# remote_control.net
KiCad netlist of a schematic drawn in EAGLE
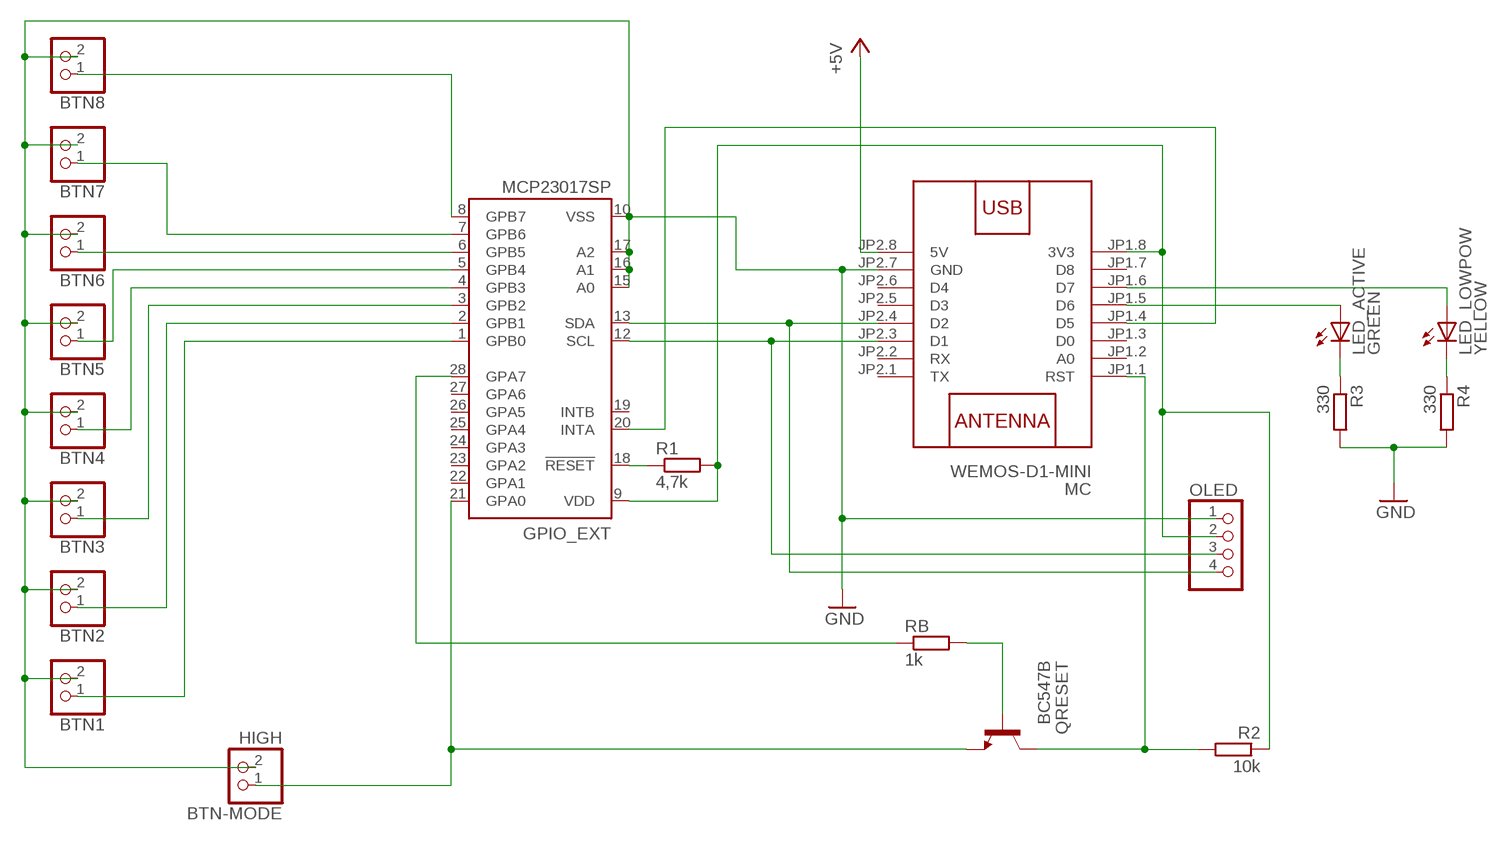
[diagram p0: schematic, sheet 1]

(export (version "E")
  (design (tool "Eeschema 10.0.6"))
  (components
    (comp (ref "BTN-MODE")
      (value "HIGH")
      (footprint "eagle-import:1X02")
      (libsource (lib "eagle-import") (part "PINHD-1X2"))
    )
    (comp (ref "BTN1")
      (value "HIGH")
      (footprint "eagle-import:1X02")
      (libsource (lib "eagle-import") (part "PINHD-1X2"))
    )
    (comp (ref "BTN2")
      (value "HIGH")
      (footprint "eagle-import:1X02")
      (libsource (lib "eagle-import") (part "PINHD-1X2"))
    )
    (comp (ref "BTN3")
      (value "PINHD-1X2")
      (footprint "eagle-import:1X02")
      (libsource (lib "eagle-import") (part "PINHD-1X2"))
    )
    (comp (ref "BTN4")
      (value "PINHD-1X2")
      (footprint "eagle-import:1X02")
      (libsource (lib "eagle-import") (part "PINHD-1X2"))
    )
    (comp (ref "BTN5")
      (value "PINHD-1X2")
      (footprint "eagle-import:1X02")
      (libsource (lib "eagle-import") (part "PINHD-1X2"))
    )
    (comp (ref "BTN6")
      (value "PINHD-1X2")
      (footprint "eagle-import:1X02")
      (libsource (lib "eagle-import") (part "PINHD-1X2"))
    )
    (comp (ref "BTN7")
      (value "PINHD-1X2")
      (footprint "eagle-import:1X02")
      (libsource (lib "eagle-import") (part "PINHD-1X2"))
    )
    (comp (ref "BTN8")
      (value "PINHD-1X2")
      (footprint "eagle-import:1X02")
      (libsource (lib "eagle-import") (part "PINHD-1X2"))
    )
    (comp (ref "GPIO_EXT")
      (value "MCP23017SP")
      (footprint "eagle-import:DIL28-3")
      (fields (field (name "MF") "MICROCHIP") (field (name "MPN") "MCP23017-E/SP"))
      (libsource (lib "eagle-import") (part "MCP23017SP"))
    )
    (comp (ref "LED_ACTIVE")
      (value "GREEN")
      (footprint "eagle-import:LED3MM")
      (libsource (lib "eagle-import") (part "LED3MM"))
    )
    (comp (ref "LED_LOWPOW")
      (value "YELLOW")
      (footprint "eagle-import:LED3MM")
      (libsource (lib "eagle-import") (part "LED3MM"))
    )
    (comp (ref "MC")
      (value "WEMOS-D1-MINI")
      (footprint "eagle-import:WEMOS-D1-MINI")
      (libsource (lib "eagle-import") (part "WEMOS-D1-MINI"))
    )
    (comp (ref "OLED")
      (value "PINHD-1X4")
      (footprint "eagle-import:1X04")
      (libsource (lib "eagle-import") (part "PINHD-1X4"))
    )
    (comp (ref "QRESET")
      (value "BC547B")
      (footprint "eagle-import:TO92")
      (libsource (lib "eagle-import") (part "BC547B"))
    )
    (comp (ref "R1")
      (value "4,7k")
      (footprint "eagle-import:0204_5")
      (libsource (lib "eagle-import") (part "R-EU_0204/5"))
    )
    (comp (ref "R2")
      (value "10k")
      (footprint "eagle-import:0204_5")
      (libsource (lib "eagle-import") (part "R-EU_0204/5"))
    )
    (comp (ref "R3")
      (value "330")
      (footprint "eagle-import:0204_5")
      (libsource (lib "eagle-import") (part "R-EU_0204/5"))
    )
    (comp (ref "R4")
      (value "330")
      (footprint "eagle-import:0204_5")
      (libsource (lib "eagle-import") (part "R-EU_0204/5"))
    )
    (comp (ref "RB")
      (value "1k")
      (footprint "eagle-import:0204_5")
      (libsource (lib "eagle-import") (part "R-EU_0204/5"))
    )
  )
  (nets
    (net (code "1") (name "+5V") (class "Default")
      (node (ref "MC") (pin "JP2.8") (pinfunction "5V_JP2.8") (pintype "power_in"))
    )
    (net (code "2") (name "GND") (class "Default")
      (node (ref "BTN-MODE") (pin "2") (pinfunction "2_2") (pintype "passive"))
      (node (ref "BTN1") (pin "2") (pinfunction "2_2") (pintype "passive"))
      (node (ref "BTN2") (pin "2") (pinfunction "2_2") (pintype "passive"))
      (node (ref "BTN3") (pin "2") (pinfunction "2_2") (pintype "passive"))
      (node (ref "BTN4") (pin "2") (pinfunction "2_2") (pintype "passive"))
      (node (ref "BTN5") (pin "2") (pinfunction "2_2") (pintype "passive"))
      (node (ref "BTN6") (pin "2") (pinfunction "2_2") (pintype "passive"))
      (node (ref "BTN7") (pin "2") (pinfunction "2_2") (pintype "passive"))
      (node (ref "BTN8") (pin "2") (pinfunction "2_2") (pintype "passive"))
      (node (ref "GPIO_EXT") (pin "10") (pinfunction "VSS_10") (pintype "power_in"))
      (node (ref "GPIO_EXT") (pin "15") (pinfunction "A0_15") (pintype "input"))
      (node (ref "GPIO_EXT") (pin "16") (pinfunction "A1_16") (pintype "input"))
      (node (ref "GPIO_EXT") (pin "17") (pinfunction "A2_17") (pintype "input"))
      (node (ref "MC") (pin "JP2.7") (pinfunction "GND_JP2.7") (pintype "power_in"))
      (node (ref "OLED") (pin "1") (pinfunction "1_1") (pintype "passive"))
      (node (ref "R3") (pin "2") (pinfunction "2_2") (pintype "passive"))
      (node (ref "R4") (pin "2") (pinfunction "2_2") (pintype "passive"))
    )
    (net (code "3") (name "Net-(GPIO_EXT-GPA0)") (class "Default")
      (node (ref "BTN-MODE") (pin "1") (pinfunction "1_1") (pintype "passive"))
      (node (ref "GPIO_EXT") (pin "21") (pinfunction "GPA0_21") (pintype "bidirectional"))
      (node (ref "QRESET") (pin "1") (pinfunction "E_1") (pintype "passive"))
    )
    (net (code "4") (name "Net-(GPIO_EXT-GPA7)") (class "Default")
      (node (ref "GPIO_EXT") (pin "28") (pinfunction "GPA7_28") (pintype "bidirectional"))
      (node (ref "RB") (pin "1") (pinfunction "1_1") (pintype "passive"))
    )
    (net (code "5") (name "Net-(GPIO_EXT-GPB0)") (class "Default")
      (node (ref "BTN1") (pin "1") (pinfunction "1_1") (pintype "passive"))
      (node (ref "GPIO_EXT") (pin "1") (pinfunction "GPB0_1") (pintype "bidirectional"))
    )
    (net (code "6") (name "Net-(GPIO_EXT-GPB1)") (class "Default")
      (node (ref "BTN2") (pin "1") (pinfunction "1_1") (pintype "passive"))
      (node (ref "GPIO_EXT") (pin "2") (pinfunction "GPB1_2") (pintype "bidirectional"))
    )
    (net (code "7") (name "Net-(GPIO_EXT-GPB2)") (class "Default")
      (node (ref "BTN3") (pin "1") (pinfunction "1_1") (pintype "passive"))
      (node (ref "GPIO_EXT") (pin "3") (pinfunction "GPB2_3") (pintype "bidirectional"))
    )
    (net (code "8") (name "Net-(GPIO_EXT-GPB3)") (class "Default")
      (node (ref "BTN4") (pin "1") (pinfunction "1_1") (pintype "passive"))
      (node (ref "GPIO_EXT") (pin "4") (pinfunction "GPB3_4") (pintype "bidirectional"))
    )
    (net (code "9") (name "Net-(GPIO_EXT-GPB4)") (class "Default")
      (node (ref "BTN5") (pin "1") (pinfunction "1_1") (pintype "passive"))
      (node (ref "GPIO_EXT") (pin "5") (pinfunction "GPB4_5") (pintype "bidirectional"))
    )
    (net (code "10") (name "Net-(GPIO_EXT-GPB5)") (class "Default")
      (node (ref "BTN6") (pin "1") (pinfunction "1_1") (pintype "passive"))
      (node (ref "GPIO_EXT") (pin "6") (pinfunction "GPB5_6") (pintype "bidirectional"))
    )
    (net (code "11") (name "Net-(GPIO_EXT-GPB6)") (class "Default")
      (node (ref "BTN7") (pin "1") (pinfunction "1_1") (pintype "passive"))
      (node (ref "GPIO_EXT") (pin "7") (pinfunction "GPB6_7") (pintype "bidirectional"))
    )
    (net (code "12") (name "Net-(GPIO_EXT-GPB7)") (class "Default")
      (node (ref "BTN8") (pin "1") (pinfunction "1_1") (pintype "passive"))
      (node (ref "GPIO_EXT") (pin "8") (pinfunction "GPB7_8") (pintype "bidirectional"))
    )
    (net (code "13") (name "Net-(GPIO_EXT-INTA)") (class "Default")
      (node (ref "GPIO_EXT") (pin "20") (pinfunction "INTA_20") (pintype "output"))
      (node (ref "MC") (pin "JP1.4") (pinfunction "D5_JP1.4") (pintype "bidirectional"))
    )
    (net (code "14") (name "Net-(GPIO_EXT-SCL)") (class "Default")
      (node (ref "GPIO_EXT") (pin "12") (pinfunction "SCL_12") (pintype "input"))
      (node (ref "MC") (pin "JP2.3") (pinfunction "D1_JP2.3") (pintype "bidirectional"))
      (node (ref "OLED") (pin "3") (pinfunction "3_3") (pintype "passive"))
    )
    (net (code "15") (name "Net-(GPIO_EXT-SDA)") (class "Default")
      (node (ref "GPIO_EXT") (pin "13") (pinfunction "SDA_13") (pintype "bidirectional"))
      (node (ref "MC") (pin "JP2.4") (pinfunction "D2_JP2.4") (pintype "bidirectional"))
      (node (ref "OLED") (pin "4") (pinfunction "4_4") (pintype "passive"))
    )
    (net (code "16") (name "Net-(GPIO_EXT-VDD)") (class "Default")
      (node (ref "GPIO_EXT") (pin "9") (pinfunction "VDD_9") (pintype "power_in"))
      (node (ref "MC") (pin "JP1.8") (pinfunction "3V3_JP1.8") (pintype "power_in"))
      (node (ref "OLED") (pin "2") (pinfunction "2_2") (pintype "passive"))
      (node (ref "R1") (pin "2") (pinfunction "2_2") (pintype "passive"))
      (node (ref "R2") (pin "1") (pinfunction "1_1") (pintype "passive"))
    )
    (net (code "17") (name "Net-(GPIO_EXT-~{RESET})") (class "Default")
      (node (ref "GPIO_EXT") (pin "18") (pinfunction "~{RESET}_18") (pintype "input"))
      (node (ref "R1") (pin "1") (pinfunction "1_1") (pintype "passive"))
    )
    (net (code "18") (name "Net-(LED_ACTIVE-C)") (class "Default")
      (node (ref "LED_ACTIVE") (pin "K") (pinfunction "C_K") (pintype "passive"))
      (node (ref "R3") (pin "1") (pinfunction "1_1") (pintype "passive"))
    )
    (net (code "19") (name "Net-(LED_LOWPOW-C)") (class "Default")
      (node (ref "LED_LOWPOW") (pin "K") (pinfunction "C_K") (pintype "passive"))
      (node (ref "R4") (pin "1") (pinfunction "1_1") (pintype "passive"))
    )
    (net (code "20") (name "Net-(MC-D6)") (class "Default")
      (node (ref "LED_ACTIVE") (pin "A") (pinfunction "A_A") (pintype "passive"))
      (node (ref "MC") (pin "JP1.5") (pinfunction "D6_JP1.5") (pintype "bidirectional"))
    )
    (net (code "21") (name "Net-(MC-D7)") (class "Default")
      (node (ref "LED_LOWPOW") (pin "A") (pinfunction "A_A") (pintype "passive"))
      (node (ref "MC") (pin "JP1.6") (pinfunction "D7_JP1.6") (pintype "bidirectional"))
    )
    (net (code "22") (name "Net-(MC-RST)") (class "Default")
      (node (ref "MC") (pin "JP1.1") (pinfunction "RST_JP1.1") (pintype "bidirectional"))
      (node (ref "QRESET") (pin "3") (pinfunction "C_3") (pintype "passive"))
      (node (ref "R2") (pin "2") (pinfunction "2_2") (pintype "passive"))
    )
    (net (code "23") (name "Net-(QRESET-B)") (class "Default")
      (node (ref "QRESET") (pin "2") (pinfunction "B_2") (pintype "passive"))
      (node (ref "RB") (pin "2") (pinfunction "2_2") (pintype "passive"))
    )
    (net (code "24") (name "unconnected-(GPIO_EXT-GPA1-Pad22)") (class "Default")
      (node (ref "GPIO_EXT") (pin "22") (pinfunction "GPA1_22") (pintype "bidirectional"))
    )
    (net (code "25") (name "unconnected-(GPIO_EXT-GPA2-Pad23)") (class "Default")
      (node (ref "GPIO_EXT") (pin "23") (pinfunction "GPA2_23") (pintype "bidirectional"))
    )
    (net (code "26") (name "unconnected-(GPIO_EXT-GPA3-Pad24)") (class "Default")
      (node (ref "GPIO_EXT") (pin "24") (pinfunction "GPA3_24") (pintype "bidirectional"))
    )
    (net (code "27") (name "unconnected-(GPIO_EXT-GPA4-Pad25)") (class "Default")
      (node (ref "GPIO_EXT") (pin "25") (pinfunction "GPA4_25") (pintype "bidirectional"))
    )
    (net (code "28") (name "unconnected-(GPIO_EXT-GPA5-Pad26)") (class "Default")
      (node (ref "GPIO_EXT") (pin "26") (pinfunction "GPA5_26") (pintype "bidirectional"))
    )
    (net (code "29") (name "unconnected-(GPIO_EXT-GPA6-Pad27)") (class "Default")
      (node (ref "GPIO_EXT") (pin "27") (pinfunction "GPA6_27") (pintype "bidirectional"))
    )
    (net (code "30") (name "unconnected-(GPIO_EXT-INTB-Pad19)") (class "Default")
      (node (ref "GPIO_EXT") (pin "19") (pinfunction "INTB_19") (pintype "output"))
    )
    (net (code "31") (name "unconnected-(MC-A0-PadJP1.2)") (class "Default")
      (node (ref "MC") (pin "JP1.2") (pinfunction "A0_JP1.2") (pintype "bidirectional"))
    )
    (net (code "32") (name "unconnected-(MC-D0-PadJP1.3)") (class "Default")
      (node (ref "MC") (pin "JP1.3") (pinfunction "D0_JP1.3") (pintype "bidirectional"))
    )
    (net (code "33") (name "unconnected-(MC-D3-PadJP2.5)") (class "Default")
      (node (ref "MC") (pin "JP2.5") (pinfunction "D3_JP2.5") (pintype "bidirectional"))
    )
    (net (code "34") (name "unconnected-(MC-D4-PadJP2.6)") (class "Default")
      (node (ref "MC") (pin "JP2.6") (pinfunction "D4_JP2.6") (pintype "bidirectional"))
    )
    (net (code "35") (name "unconnected-(MC-D8-PadJP1.7)") (class "Default")
      (node (ref "MC") (pin "JP1.7") (pinfunction "D8_JP1.7") (pintype "bidirectional"))
    )
    (net (code "36") (name "unconnected-(MC-RX-PadJP2.2)") (class "Default")
      (node (ref "MC") (pin "JP2.2") (pinfunction "RX_JP2.2") (pintype "bidirectional"))
    )
    (net (code "37") (name "unconnected-(MC-TX-PadJP2.1)") (class "Default")
      (node (ref "MC") (pin "JP2.1") (pinfunction "TX_JP2.1") (pintype "bidirectional"))
    )
  )
)
